# din-synch-hub.net
KiCad netlist of a schematic drawn in EAGLE
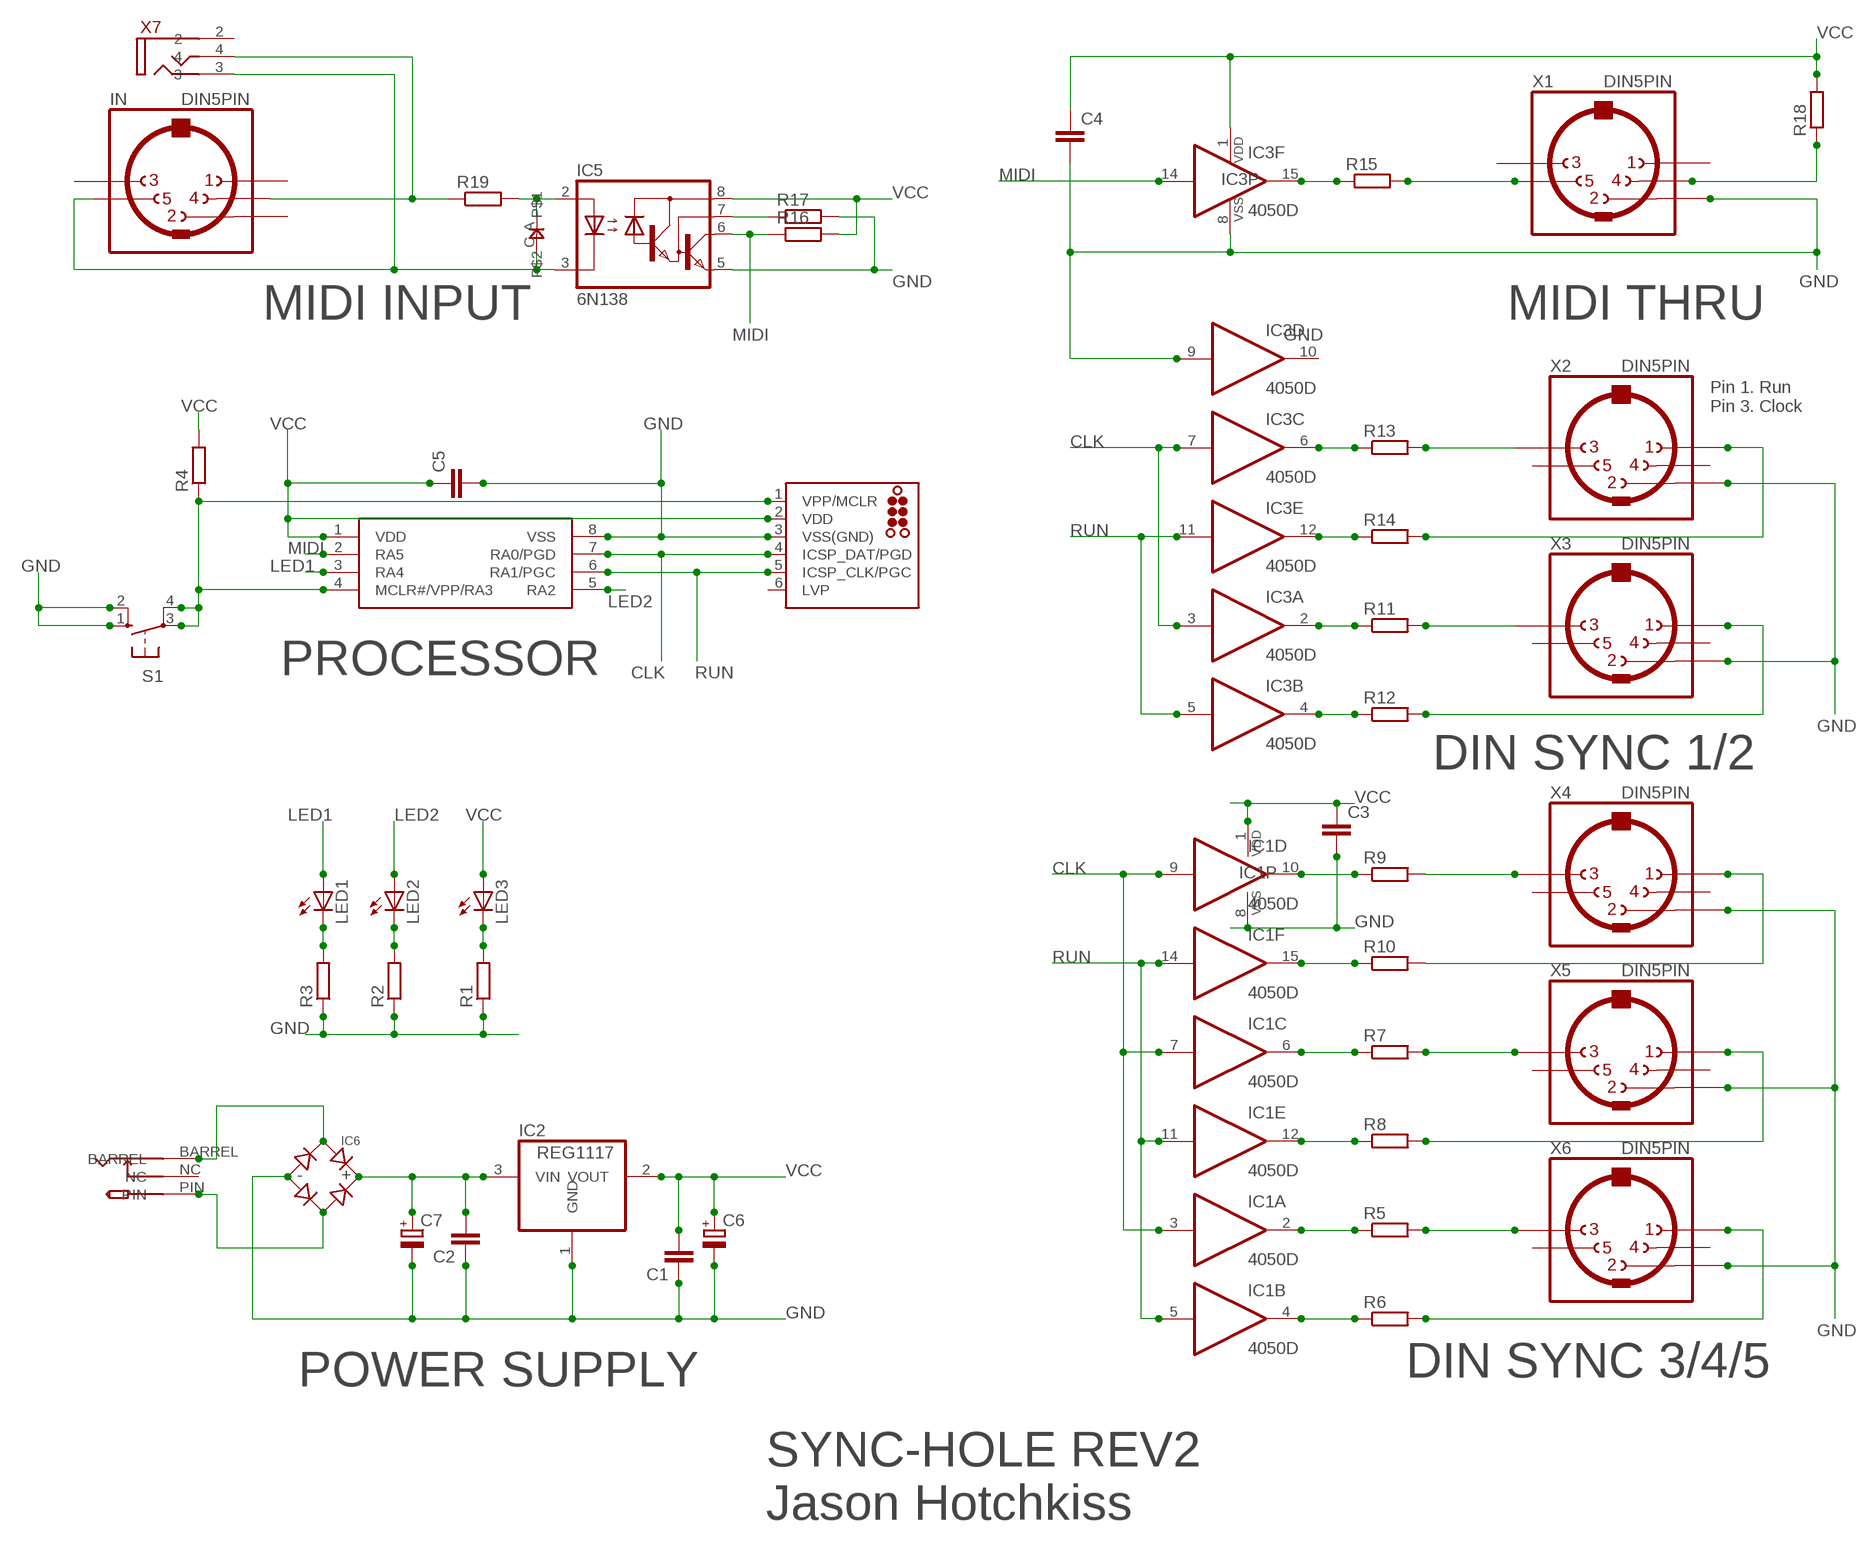
[diagram p0: schematic, sheet 1]

(export (version "E")
  (design (tool "Eeschema 10.0.6"))
  (components
    (comp (ref "C1")
      (value "C-EUC0805")
      (footprint "eagle-import:C0805")
      (libsource (lib "eagle-import") (part "C-EUC0805"))
    )
    (comp (ref "C2")
      (value "C-EUC0805")
      (footprint "eagle-import:C0805")
      (libsource (lib "eagle-import") (part "C-EUC0805"))
    )
    (comp (ref "C3")
      (value "C-EUC0805")
      (footprint "eagle-import:C0805")
      (libsource (lib "eagle-import") (part "C-EUC0805"))
    )
    (comp (ref "C4")
      (value "C-EUC0805")
      (footprint "eagle-import:C0805")
      (libsource (lib "eagle-import") (part "C-EUC0805"))
    )
    (comp (ref "C5")
      (value "C-EUC0805")
      (footprint "eagle-import:C0805")
      (libsource (lib "eagle-import") (part "C-EUC0805"))
    )
    (comp (ref "C6")
      (value "CPOL-EUE2,5-6E")
      (footprint "eagle-import:E2,5-6E")
      (libsource (lib "eagle-import") (part "CPOL-EUE2,5-6E"))
    )
    (comp (ref "C7")
      (value "CPOL-EUE2,5-6E")
      (footprint "eagle-import:E2,5-6E")
      (libsource (lib "eagle-import") (part "CPOL-EUE2,5-6E"))
    )
    (comp (ref "D1")
      (value "0805DIODE")
      (footprint "eagle-import:0805DIODE")
      (libsource (lib "eagle-import") (part "0805DIODE"))
    )
    (comp (ref "IC1")
      (value "4050D")
      (footprint "eagle-import:SO16")
      (libsource (lib "eagle-import") (part "4050D"))
    )
    (comp (ref "IC2")
      (value "REG1117")
      (footprint "eagle-import:SOT223")
      (libsource (lib "eagle-import") (part "REG1117"))
    )
    (comp (ref "IC3")
      (value "4050D")
      (footprint "eagle-import:SO16")
      (libsource (lib "eagle-import") (part "4050D"))
    )
    (comp (ref "IC4")
      (value "PIC12F1822SO08")
      (footprint "eagle-import:SO08")
      (libsource (lib "eagle-import") (part "PIC12F1822SO08"))
    )
    (comp (ref "IC5")
      (value "6N138")
      (footprint "eagle-import:DIL08")
      (fields (field (name "MF") "VISHAY/TELEFUNKEN"))
      (libsource (lib "eagle-import") (part "6N138"))
    )
    (comp (ref "IC6")
      (value "BRIDGERECTIFIER")
      (footprint "eagle-import:SOIC-4")
      (libsource (lib "eagle-import") (part "BRIDGERECTIFIER"))
    )
    (comp (ref "ICSP")
      (value "TC2030-MCP-NL")
      (footprint "eagle-import:TC2030-MCP-NL")
      (libsource (lib "eagle-import") (part "TC2030-MCP-NL"))
    )
    (comp (ref "IN")
      (value "DIN5PIN")
      (footprint "eagle-import:EDGEDIN")
      (libsource (lib "eagle-import") (part "DIN5PIN"))
    )
    (comp (ref "LED1")
      (value "LED3MM")
      (footprint "eagle-import:LED3MM")
      (libsource (lib "eagle-import") (part "LED3MM"))
    )
    (comp (ref "LED2")
      (value "LED3MM")
      (footprint "eagle-import:LED3MM")
      (libsource (lib "eagle-import") (part "LED3MM"))
    )
    (comp (ref "LED3")
      (value "LED3MM")
      (footprint "eagle-import:LED3MM")
      (libsource (lib "eagle-import") (part "LED3MM"))
    )
    (comp (ref "R1")
      (value "R-EU_R0805")
      (footprint "eagle-import:R0805")
      (libsource (lib "eagle-import") (part "R-EU_R0805"))
    )
    (comp (ref "R2")
      (value "R-EU_R0805")
      (footprint "eagle-import:R0805")
      (libsource (lib "eagle-import") (part "R-EU_R0805"))
    )
    (comp (ref "R3")
      (value "R-EU_R0805")
      (footprint "eagle-import:R0805")
      (libsource (lib "eagle-import") (part "R-EU_R0805"))
    )
    (comp (ref "R4")
      (value "R-EU_R0805")
      (footprint "eagle-import:R0805")
      (libsource (lib "eagle-import") (part "R-EU_R0805"))
    )
    (comp (ref "R5")
      (value "R-EU_R0805")
      (footprint "eagle-import:R0805")
      (libsource (lib "eagle-import") (part "R-EU_R0805"))
    )
    (comp (ref "R6")
      (value "R-EU_R0805")
      (footprint "eagle-import:R0805")
      (libsource (lib "eagle-import") (part "R-EU_R0805"))
    )
    (comp (ref "R7")
      (value "R-EU_R0805")
      (footprint "eagle-import:R0805")
      (libsource (lib "eagle-import") (part "R-EU_R0805"))
    )
    (comp (ref "R8")
      (value "R-EU_R0805")
      (footprint "eagle-import:R0805")
      (libsource (lib "eagle-import") (part "R-EU_R0805"))
    )
    (comp (ref "R9")
      (value "R-EU_R0805")
      (footprint "eagle-import:R0805")
      (libsource (lib "eagle-import") (part "R-EU_R0805"))
    )
    (comp (ref "R10")
      (value "R-EU_R0805")
      (footprint "eagle-import:R0805")
      (libsource (lib "eagle-import") (part "R-EU_R0805"))
    )
    (comp (ref "R11")
      (value "R-EU_R0805")
      (footprint "eagle-import:R0805")
      (libsource (lib "eagle-import") (part "R-EU_R0805"))
    )
    (comp (ref "R12")
      (value "R-EU_R0805")
      (footprint "eagle-import:R0805")
      (libsource (lib "eagle-import") (part "R-EU_R0805"))
    )
    (comp (ref "R13")
      (value "R-EU_R0805")
      (footprint "eagle-import:R0805")
      (libsource (lib "eagle-import") (part "R-EU_R0805"))
    )
    (comp (ref "R14")
      (value "R-EU_R0805")
      (footprint "eagle-import:R0805")
      (libsource (lib "eagle-import") (part "R-EU_R0805"))
    )
    (comp (ref "R15")
      (value "R-EU_R0805")
      (footprint "eagle-import:R0805")
      (libsource (lib "eagle-import") (part "R-EU_R0805"))
    )
    (comp (ref "R16")
      (value "R-EU_R0805")
      (footprint "eagle-import:R0805")
      (libsource (lib "eagle-import") (part "R-EU_R0805"))
    )
    (comp (ref "R17")
      (value "R-EU_R0805")
      (footprint "eagle-import:R0805")
      (libsource (lib "eagle-import") (part "R-EU_R0805"))
    )
    (comp (ref "R18")
      (value "R-EU_R0805")
      (footprint "eagle-import:R0805")
      (libsource (lib "eagle-import") (part "R-EU_R0805"))
    )
    (comp (ref "R19")
      (value "R-EU_R0805")
      (footprint "eagle-import:R0805")
      (libsource (lib "eagle-import") (part "R-EU_R0805"))
    )
    (comp (ref "S1")
      (value "10-XX")
      (footprint "eagle-import:B3F-10XX")
      (fields (field (name "MPN") "B3F-1000"))
      (libsource (lib "eagle-import") (part "10-XX"))
    )
    (comp (ref "U$1")
      (value "PWR_SOCKET_2_1MM")
      (footprint "eagle-import:PWR_SOCKET_2_1MM")
      (libsource (lib "eagle-import") (part "PWR_SOCKET_2_1MM"))
    )
    (comp (ref "X1")
      (value "DIN5PIN")
      (footprint "eagle-import:EDGEDIN")
      (libsource (lib "eagle-import") (part "DIN5PIN"))
    )
    (comp (ref "X2")
      (value "DIN5PIN")
      (footprint "eagle-import:EDGEDIN")
      (libsource (lib "eagle-import") (part "DIN5PIN"))
    )
    (comp (ref "X3")
      (value "DIN5PIN")
      (footprint "eagle-import:EDGEDIN")
      (libsource (lib "eagle-import") (part "DIN5PIN"))
    )
    (comp (ref "X4")
      (value "DIN5PIN")
      (footprint "eagle-import:EDGEDIN")
      (libsource (lib "eagle-import") (part "DIN5PIN"))
    )
    (comp (ref "X5")
      (value "DIN5PIN")
      (footprint "eagle-import:EDGEDIN")
      (libsource (lib "eagle-import") (part "DIN5PIN"))
    )
    (comp (ref "X6")
      (value "DIN5PIN")
      (footprint "eagle-import:EDGEDIN")
      (libsource (lib "eagle-import") (part "DIN5PIN"))
    )
    (comp (ref "X7")
      (value "VERTICAL_3_5MM_SOCKET")
      (footprint "eagle-import:VERTICAL_3_5MM_SOCKET")
      (libsource (lib "eagle-import") (part "VERTICAL_3_5MM_SOCKET"))
    )
  )
  (nets
    (net (code "1") (name "/CLK") (class "Default")
      (node (ref "IC1") (pin "3") (pinfunction "I_3") (pintype "input"))
      (node (ref "IC1") (pin "7") (pinfunction "I_7") (pintype "input"))
      (node (ref "IC1") (pin "9") (pinfunction "I_9") (pintype "input"))
      (node (ref "IC3") (pin "3") (pinfunction "I_3") (pintype "input"))
      (node (ref "IC3") (pin "7") (pinfunction "I_7") (pintype "input"))
      (node (ref "IC4") (pin "7") (pinfunction "RA0/PGD_7") (pintype "bidirectional"))
      (node (ref "ICSP") (pin "4") (pinfunction "ICSP_DAT/PGD_4") (pintype "bidirectional"))
    )
    (net (code "2") (name "/GND") (class "Default")
      (node (ref "C1") (pin "1") (pinfunction "1_1") (pintype "passive"))
      (node (ref "C2") (pin "1") (pinfunction "1_1") (pintype "passive"))
      (node (ref "C3") (pin "2") (pinfunction "2_2") (pintype "passive"))
      (node (ref "C4") (pin "2") (pinfunction "2_2") (pintype "passive"))
      (node (ref "C5") (pin "2") (pinfunction "2_2") (pintype "passive"))
      (node (ref "C6") (pin "-") (pinfunction "-_-") (pintype "passive"))
      (node (ref "C7") (pin "-") (pinfunction "-_-") (pintype "passive"))
      (node (ref "IC1") (pin "8") (pinfunction "VSS_8") (pintype "power_in"))
      (node (ref "IC2") (pin "1") (pinfunction "GND_1") (pintype "power_in"))
      (node (ref "IC3") (pin "8") (pinfunction "VSS_8") (pintype "power_in"))
      (node (ref "IC3") (pin "9") (pinfunction "I_9") (pintype "input"))
      (node (ref "IC4") (pin "8") (pinfunction "VSS_8") (pintype "power_in"))
      (node (ref "IC5") (pin "5") (pinfunction "GND_5") (pintype "passive"))
      (node (ref "IC6") (pin "-") (pinfunction "-_-") (pintype "passive"))
      (node (ref "ICSP") (pin "3") (pinfunction "VSS(GND)_3") (pintype "power_in"))
      (node (ref "R1") (pin "1") (pinfunction "1_1") (pintype "passive"))
      (node (ref "R17") (pin "2") (pinfunction "2_2") (pintype "passive"))
      (node (ref "R2") (pin "1") (pinfunction "1_1") (pintype "passive"))
      (node (ref "R3") (pin "1") (pinfunction "1_1") (pintype "passive"))
      (node (ref "S1") (pin "1") (pinfunction "S_1") (pintype "passive"))
      (node (ref "S1") (pin "2") (pinfunction "S1_2") (pintype "passive"))
      (node (ref "X1") (pin "2") (pinfunction "2_2") (pintype "passive"))
      (node (ref "X2") (pin "2") (pinfunction "2_2") (pintype "passive"))
      (node (ref "X3") (pin "2") (pinfunction "2_2") (pintype "passive"))
      (node (ref "X4") (pin "2") (pinfunction "2_2") (pintype "passive"))
      (node (ref "X5") (pin "2") (pinfunction "2_2") (pintype "passive"))
      (node (ref "X6") (pin "2") (pinfunction "2_2") (pintype "passive"))
    )
    (net (code "3") (name "/LED1") (class "Default")
      (node (ref "IC4") (pin "3") (pinfunction "RA4_3") (pintype "bidirectional"))
      (node (ref "LED1") (pin "A") (pinfunction "A_A") (pintype "passive"))
    )
    (net (code "4") (name "/LED2") (class "Default")
      (node (ref "IC4") (pin "5") (pinfunction "RA2_5") (pintype "bidirectional"))
      (node (ref "LED2") (pin "A") (pinfunction "A_A") (pintype "passive"))
    )
    (net (code "5") (name "/MIDI") (class "Default")
      (node (ref "IC3") (pin "14") (pinfunction "I_14") (pintype "input"))
      (node (ref "IC4") (pin "2") (pinfunction "RA5_2") (pintype "bidirectional"))
      (node (ref "IC5") (pin "6") (pinfunction "VO_6") (pintype "passive"))
      (node (ref "R16") (pin "1") (pinfunction "1_1") (pintype "passive"))
    )
    (net (code "6") (name "/RUN") (class "Default")
      (node (ref "IC1") (pin "11") (pinfunction "I_11") (pintype "input"))
      (node (ref "IC1") (pin "14") (pinfunction "I_14") (pintype "input"))
      (node (ref "IC1") (pin "5") (pinfunction "I_5") (pintype "input"))
      (node (ref "IC3") (pin "11") (pinfunction "I_11") (pintype "input"))
      (node (ref "IC3") (pin "5") (pinfunction "I_5") (pintype "input"))
      (node (ref "IC4") (pin "6") (pinfunction "RA1/PGC_6") (pintype "bidirectional"))
      (node (ref "ICSP") (pin "5") (pinfunction "ICSP_CLK/PGC_5") (pintype "output"))
    )
    (net (code "7") (name "/VCC") (class "Default")
      (node (ref "C1") (pin "2") (pinfunction "2_2") (pintype "passive"))
      (node (ref "C3") (pin "1") (pinfunction "1_1") (pintype "passive"))
      (node (ref "C4") (pin "1") (pinfunction "1_1") (pintype "passive"))
      (node (ref "C5") (pin "1") (pinfunction "1_1") (pintype "passive"))
      (node (ref "C6") (pin "+") (pinfunction "+_+") (pintype "passive"))
      (node (ref "IC1") (pin "1") (pinfunction "VDD_1") (pintype "power_in"))
      (node (ref "IC2") (pin "2") (pinfunction "VOUT_2") (pintype "output"))
      (node (ref "IC3") (pin "1") (pinfunction "VDD_1") (pintype "power_in"))
      (node (ref "IC4") (pin "1") (pinfunction "VDD_1") (pintype "power_in"))
      (node (ref "IC5") (pin "8") (pinfunction "VCC_8") (pintype "passive"))
      (node (ref "ICSP") (pin "2") (pinfunction "VDD_2") (pintype "power_in"))
      (node (ref "LED3") (pin "A") (pinfunction "A_A") (pintype "passive"))
      (node (ref "R16") (pin "2") (pinfunction "2_2") (pintype "passive"))
      (node (ref "R18") (pin "2") (pinfunction "2_2") (pintype "passive"))
      (node (ref "R4") (pin "2") (pinfunction "2_2") (pintype "passive"))
    )
    (net (code "8") (name "Net-(D1-P$1)") (class "Default")
      (node (ref "D1") (pin "C") (pinfunction "P$1_C") (pintype "bidirectional"))
      (node (ref "IC5") (pin "3") (pinfunction "C_3") (pintype "passive"))
      (node (ref "IN") (pin "5") (pinfunction "5_5") (pintype "passive"))
      (node (ref "X7") (pin "3") (pinfunction "3_3") (pintype "bidirectional"))
    )
    (net (code "9") (name "Net-(D1-P$2)") (class "Default")
      (node (ref "D1") (pin "A") (pinfunction "P$2_A") (pintype "bidirectional"))
      (node (ref "IC5") (pin "2") (pinfunction "A_2") (pintype "passive"))
      (node (ref "R19") (pin "2") (pinfunction "2_2") (pintype "passive"))
    )
    (net (code "10") (name "Net-(IC1A-O)") (class "Default")
      (node (ref "IC1") (pin "2") (pinfunction "O_2") (pintype "output"))
      (node (ref "R5") (pin "1") (pinfunction "1_1") (pintype "passive"))
    )
    (net (code "11") (name "Net-(IC1B-O)") (class "Default")
      (node (ref "IC1") (pin "4") (pinfunction "O_4") (pintype "output"))
      (node (ref "R6") (pin "1") (pinfunction "1_1") (pintype "passive"))
    )
    (net (code "12") (name "Net-(IC1C-O)") (class "Default")
      (node (ref "IC1") (pin "6") (pinfunction "O_6") (pintype "output"))
      (node (ref "R7") (pin "1") (pinfunction "1_1") (pintype "passive"))
    )
    (net (code "13") (name "Net-(IC1D-O)") (class "Default")
      (node (ref "IC1") (pin "10") (pinfunction "O_10") (pintype "output"))
      (node (ref "R9") (pin "1") (pinfunction "1_1") (pintype "passive"))
    )
    (net (code "14") (name "Net-(IC1E-O)") (class "Default")
      (node (ref "IC1") (pin "12") (pinfunction "O_12") (pintype "output"))
      (node (ref "R8") (pin "1") (pinfunction "1_1") (pintype "passive"))
    )
    (net (code "15") (name "Net-(IC1F-O)") (class "Default")
      (node (ref "IC1") (pin "15") (pinfunction "O_15") (pintype "output"))
      (node (ref "R10") (pin "1") (pinfunction "1_1") (pintype "passive"))
    )
    (net (code "16") (name "Net-(IC2-VIN)") (class "Default")
      (node (ref "C2") (pin "2") (pinfunction "2_2") (pintype "passive"))
      (node (ref "C7") (pin "+") (pinfunction "+_+") (pintype "passive"))
      (node (ref "IC2") (pin "3") (pinfunction "VIN_3") (pintype "input"))
      (node (ref "IC6") (pin "+") (pinfunction "+_+") (pintype "passive"))
    )
    (net (code "17") (name "Net-(IC3A-O)") (class "Default")
      (node (ref "IC3") (pin "2") (pinfunction "O_2") (pintype "output"))
      (node (ref "R11") (pin "1") (pinfunction "1_1") (pintype "passive"))
    )
    (net (code "18") (name "Net-(IC3B-O)") (class "Default")
      (node (ref "IC3") (pin "4") (pinfunction "O_4") (pintype "output"))
      (node (ref "R12") (pin "1") (pinfunction "1_1") (pintype "passive"))
    )
    (net (code "19") (name "Net-(IC3C-O)") (class "Default")
      (node (ref "IC3") (pin "6") (pinfunction "O_6") (pintype "output"))
      (node (ref "R13") (pin "1") (pinfunction "1_1") (pintype "passive"))
    )
    (net (code "20") (name "Net-(IC3E-O)") (class "Default")
      (node (ref "IC3") (pin "12") (pinfunction "O_12") (pintype "output"))
      (node (ref "R14") (pin "1") (pinfunction "1_1") (pintype "passive"))
    )
    (net (code "21") (name "Net-(IC3F-O)") (class "Default")
      (node (ref "IC3") (pin "15") (pinfunction "O_15") (pintype "output"))
      (node (ref "R15") (pin "1") (pinfunction "1_1") (pintype "passive"))
    )
    (net (code "22") (name "Net-(IC4-MCLR#{slash}VPP{slash}RA3)") (class "Default")
      (node (ref "IC4") (pin "4") (pinfunction "MCLR#/VPP/RA3_4") (pintype "bidirectional"))
      (node (ref "ICSP") (pin "1") (pinfunction "VPP/MCLR_1") (pintype "passive"))
      (node (ref "R4") (pin "1") (pinfunction "1_1") (pintype "passive"))
      (node (ref "S1") (pin "3") (pinfunction "P_3") (pintype "passive"))
      (node (ref "S1") (pin "4") (pinfunction "P1_4") (pintype "passive"))
    )
    (net (code "23") (name "Net-(IC5-VB)") (class "Default")
      (node (ref "IC5") (pin "7") (pinfunction "VB_7") (pintype "passive"))
      (node (ref "R17") (pin "1") (pinfunction "1_1") (pintype "passive"))
    )
    (net (code "24") (name "Net-(IC6-AC1)") (class "Default")
      (node (ref "IC6") (pin "~1") (pinfunction "AC1_~1") (pintype "passive"))
      (node (ref "U$1") (pin "BARREL") (pinfunction "BARREL_BARREL") (pintype "bidirectional"))
    )
    (net (code "25") (name "Net-(IC6-AC2)") (class "Default")
      (node (ref "IC6") (pin "~2") (pinfunction "AC2_~2") (pintype "passive"))
      (node (ref "U$1") (pin "PIN") (pinfunction "PIN_PIN") (pintype "bidirectional"))
    )
    (net (code "26") (name "Net-(IN-Pad4)") (class "Default")
      (node (ref "IN") (pin "4") (pinfunction "4_4") (pintype "passive"))
      (node (ref "R19") (pin "1") (pinfunction "1_1") (pintype "passive"))
      (node (ref "X7") (pin "4") (pinfunction "4_4") (pintype "bidirectional"))
    )
    (net (code "27") (name "Net-(LED1-C)") (class "Default")
      (node (ref "LED1") (pin "K") (pinfunction "C_K") (pintype "passive"))
      (node (ref "R3") (pin "2") (pinfunction "2_2") (pintype "passive"))
    )
    (net (code "28") (name "Net-(LED2-C)") (class "Default")
      (node (ref "LED2") (pin "K") (pinfunction "C_K") (pintype "passive"))
      (node (ref "R2") (pin "2") (pinfunction "2_2") (pintype "passive"))
    )
    (net (code "29") (name "Net-(LED3-C)") (class "Default")
      (node (ref "LED3") (pin "K") (pinfunction "C_K") (pintype "passive"))
      (node (ref "R1") (pin "2") (pinfunction "2_2") (pintype "passive"))
    )
    (net (code "30") (name "Net-(R5-Pad2)") (class "Default")
      (node (ref "R5") (pin "2") (pinfunction "2_2") (pintype "passive"))
      (node (ref "X6") (pin "3") (pinfunction "3_3") (pintype "passive"))
    )
    (net (code "31") (name "Net-(R6-Pad2)") (class "Default")
      (node (ref "R6") (pin "2") (pinfunction "2_2") (pintype "passive"))
      (node (ref "X6") (pin "1") (pinfunction "1_1") (pintype "passive"))
    )
    (net (code "32") (name "Net-(R7-Pad2)") (class "Default")
      (node (ref "R7") (pin "2") (pinfunction "2_2") (pintype "passive"))
      (node (ref "X5") (pin "3") (pinfunction "3_3") (pintype "passive"))
    )
    (net (code "33") (name "Net-(R8-Pad2)") (class "Default")
      (node (ref "R8") (pin "2") (pinfunction "2_2") (pintype "passive"))
      (node (ref "X5") (pin "1") (pinfunction "1_1") (pintype "passive"))
    )
    (net (code "34") (name "Net-(R9-Pad2)") (class "Default")
      (node (ref "R9") (pin "2") (pinfunction "2_2") (pintype "passive"))
      (node (ref "X4") (pin "3") (pinfunction "3_3") (pintype "passive"))
    )
    (net (code "35") (name "Net-(R10-Pad2)") (class "Default")
      (node (ref "R10") (pin "2") (pinfunction "2_2") (pintype "passive"))
      (node (ref "X4") (pin "1") (pinfunction "1_1") (pintype "passive"))
    )
    (net (code "36") (name "Net-(R11-Pad2)") (class "Default")
      (node (ref "R11") (pin "2") (pinfunction "2_2") (pintype "passive"))
      (node (ref "X3") (pin "3") (pinfunction "3_3") (pintype "passive"))
    )
    (net (code "37") (name "Net-(R12-Pad2)") (class "Default")
      (node (ref "R12") (pin "2") (pinfunction "2_2") (pintype "passive"))
      (node (ref "X3") (pin "1") (pinfunction "1_1") (pintype "passive"))
    )
    (net (code "38") (name "Net-(R13-Pad2)") (class "Default")
      (node (ref "R13") (pin "2") (pinfunction "2_2") (pintype "passive"))
      (node (ref "X2") (pin "3") (pinfunction "3_3") (pintype "passive"))
    )
    (net (code "39") (name "Net-(R14-Pad2)") (class "Default")
      (node (ref "R14") (pin "2") (pinfunction "2_2") (pintype "passive"))
      (node (ref "X2") (pin "1") (pinfunction "1_1") (pintype "passive"))
    )
    (net (code "40") (name "Net-(R15-Pad2)") (class "Default")
      (node (ref "R15") (pin "2") (pinfunction "2_2") (pintype "passive"))
      (node (ref "X1") (pin "5") (pinfunction "5_5") (pintype "passive"))
    )
    (net (code "41") (name "Net-(R18-Pad1)") (class "Default")
      (node (ref "R18") (pin "1") (pinfunction "1_1") (pintype "passive"))
      (node (ref "X1") (pin "4") (pinfunction "4_4") (pintype "passive"))
    )
    (net (code "42") (name "unconnected-(IC3D-O-Pad10)") (class "Default")
      (node (ref "IC3") (pin "10") (pinfunction "O_10") (pintype "output"))
    )
    (net (code "43") (name "unconnected-(ICSP-LVP-Pad6)") (class "Default")
      (node (ref "ICSP") (pin "6") (pinfunction "LVP_6") (pintype "bidirectional"))
    )
    (net (code "44") (name "unconnected-(IN-Pad1)") (class "Default")
      (node (ref "IN") (pin "1") (pinfunction "1_1") (pintype "passive"))
    )
    (net (code "45") (name "unconnected-(IN-Pad2)") (class "Default")
      (node (ref "IN") (pin "2") (pinfunction "2_2") (pintype "passive"))
    )
    (net (code "46") (name "unconnected-(IN-Pad3)") (class "Default")
      (node (ref "IN") (pin "3") (pinfunction "3_3") (pintype "passive"))
    )
    (net (code "47") (name "unconnected-(U$1-PadNC)") (class "Default")
      (node (ref "U$1") (pin "NC") (pinfunction "NC_NC") (pintype "bidirectional"))
    )
    (net (code "48") (name "unconnected-(X1-Pad1)") (class "Default")
      (node (ref "X1") (pin "1") (pinfunction "1_1") (pintype "passive"))
    )
    (net (code "49") (name "unconnected-(X1-Pad3)") (class "Default")
      (node (ref "X1") (pin "3") (pinfunction "3_3") (pintype "passive"))
    )
    (net (code "50") (name "unconnected-(X2-Pad4)") (class "Default")
      (node (ref "X2") (pin "4") (pinfunction "4_4") (pintype "passive"))
    )
    (net (code "51") (name "unconnected-(X2-Pad5)") (class "Default")
      (node (ref "X2") (pin "5") (pinfunction "5_5") (pintype "passive"))
    )
    (net (code "52") (name "unconnected-(X3-Pad4)") (class "Default")
      (node (ref "X3") (pin "4") (pinfunction "4_4") (pintype "passive"))
    )
    (net (code "53") (name "unconnected-(X3-Pad5)") (class "Default")
      (node (ref "X3") (pin "5") (pinfunction "5_5") (pintype "passive"))
    )
    (net (code "54") (name "unconnected-(X4-Pad4)") (class "Default")
      (node (ref "X4") (pin "4") (pinfunction "4_4") (pintype "passive"))
    )
    (net (code "55") (name "unconnected-(X4-Pad5)") (class "Default")
      (node (ref "X4") (pin "5") (pinfunction "5_5") (pintype "passive"))
    )
    (net (code "56") (name "unconnected-(X5-Pad4)") (class "Default")
      (node (ref "X5") (pin "4") (pinfunction "4_4") (pintype "passive"))
    )
    (net (code "57") (name "unconnected-(X5-Pad5)") (class "Default")
      (node (ref "X5") (pin "5") (pinfunction "5_5") (pintype "passive"))
    )
    (net (code "58") (name "unconnected-(X6-Pad4)") (class "Default")
      (node (ref "X6") (pin "4") (pinfunction "4_4") (pintype "passive"))
    )
    (net (code "59") (name "unconnected-(X6-Pad5)") (class "Default")
      (node (ref "X6") (pin "5") (pinfunction "5_5") (pintype "passive"))
    )
    (net (code "60") (name "unconnected-(X7-Pad2)") (class "Default")
      (node (ref "X7") (pin "2") (pinfunction "2_2") (pintype "bidirectional"))
    )
  )
)
